# board.net
KiCad netlist of a schematic drawn in EAGLE
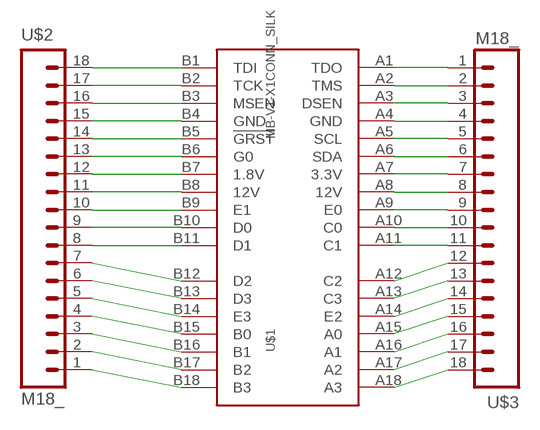
[diagram p0: schematic, sheet 1]

(export (version "E")
  (design (tool "Eeschema 10.0.6"))
  (components
    (comp (ref "U$1")
      (value "MB-V1-X1CONN_SILK")
      (footprint "eagle-import:MB-V1-X1-CONN")
      (libsource (lib "eagle-import") (part "MB-V1-X1CONN_SILK"))
    )
    (comp (ref "U$2")
      (value "M18_")
      (footprint "eagle-import:1X18")
      (libsource (lib "eagle-import") (part "M18_"))
    )
    (comp (ref "U$3")
      (value "M18_")
      (footprint "eagle-import:1X18")
      (libsource (lib "eagle-import") (part "M18_"))
    )
  )
  (nets
    (net (code "1") (name "/12V") (class "Default")
      (node (ref "U$1") (pin "A8") (pinfunction "12V_A8") (pintype "bidirectional"))
      (node (ref "U$1") (pin "B8") (pinfunction "12V_B8") (pintype "bidirectional"))
      (node (ref "U$2") (pin "11") (pinfunction "11_11") (pintype "passive"))
      (node (ref "U$3") (pin "8") (pinfunction "8_8") (pintype "passive"))
    )
    (net (code "2") (name "/GND") (class "Default")
      (node (ref "U$1") (pin "A4") (pinfunction "GND_A4") (pintype "bidirectional"))
      (node (ref "U$1") (pin "B4") (pinfunction "GND_B4") (pintype "bidirectional"))
      (node (ref "U$2") (pin "15") (pinfunction "15_15") (pintype "passive"))
      (node (ref "U$3") (pin "4") (pinfunction "4_4") (pintype "passive"))
    )
    (net (code "3") (name "Net-(U$1-1.8V)") (class "Default")
      (node (ref "U$1") (pin "B7") (pinfunction "1.8V_B7") (pintype "bidirectional"))
      (node (ref "U$2") (pin "12") (pinfunction "12_12") (pintype "passive"))
    )
    (net (code "4") (name "Net-(U$1-3.3V)") (class "Default")
      (node (ref "U$1") (pin "A7") (pinfunction "3.3V_A7") (pintype "bidirectional"))
      (node (ref "U$3") (pin "7") (pinfunction "7_7") (pintype "passive"))
    )
    (net (code "5") (name "Net-(U$1-A0)") (class "Default")
      (node (ref "U$1") (pin "A15") (pinfunction "A0_A15") (pintype "bidirectional"))
      (node (ref "U$3") (pin "15") (pinfunction "15_15") (pintype "passive"))
    )
    (net (code "6") (name "Net-(U$1-A1)") (class "Default")
      (node (ref "U$1") (pin "A16") (pinfunction "A1_A16") (pintype "bidirectional"))
      (node (ref "U$3") (pin "16") (pinfunction "16_16") (pintype "passive"))
    )
    (net (code "7") (name "Net-(U$1-A2)") (class "Default")
      (node (ref "U$1") (pin "A17") (pinfunction "A2_A17") (pintype "bidirectional"))
      (node (ref "U$3") (pin "17") (pinfunction "17_17") (pintype "passive"))
    )
    (net (code "8") (name "Net-(U$1-A3)") (class "Default")
      (node (ref "U$1") (pin "A18") (pinfunction "A3_A18") (pintype "bidirectional"))
      (node (ref "U$3") (pin "18") (pinfunction "18_18") (pintype "passive"))
    )
    (net (code "9") (name "Net-(U$1-B0)") (class "Default")
      (node (ref "U$1") (pin "B15") (pinfunction "B0_B15") (pintype "bidirectional"))
      (node (ref "U$2") (pin "4") (pinfunction "4_4") (pintype "passive"))
    )
    (net (code "10") (name "Net-(U$1-B1)") (class "Default")
      (node (ref "U$1") (pin "B16") (pinfunction "B1_B16") (pintype "bidirectional"))
      (node (ref "U$2") (pin "3") (pinfunction "3_3") (pintype "passive"))
    )
    (net (code "11") (name "Net-(U$1-B2)") (class "Default")
      (node (ref "U$1") (pin "B17") (pinfunction "B2_B17") (pintype "bidirectional"))
      (node (ref "U$2") (pin "2") (pinfunction "2_2") (pintype "passive"))
    )
    (net (code "12") (name "Net-(U$1-B3)") (class "Default")
      (node (ref "U$1") (pin "B18") (pinfunction "B3_B18") (pintype "bidirectional"))
      (node (ref "U$2") (pin "1") (pinfunction "1_1") (pintype "passive"))
    )
    (net (code "13") (name "Net-(U$1-C0)") (class "Default")
      (node (ref "U$1") (pin "A10") (pinfunction "C0_A10") (pintype "bidirectional"))
      (node (ref "U$3") (pin "10") (pinfunction "10_10") (pintype "passive"))
    )
    (net (code "14") (name "Net-(U$1-C1)") (class "Default")
      (node (ref "U$1") (pin "A11") (pinfunction "C1_A11") (pintype "bidirectional"))
      (node (ref "U$3") (pin "11") (pinfunction "11_11") (pintype "passive"))
    )
    (net (code "15") (name "Net-(U$1-C2)") (class "Default")
      (node (ref "U$1") (pin "A12") (pinfunction "C2_A12") (pintype "bidirectional"))
      (node (ref "U$3") (pin "12") (pinfunction "12_12") (pintype "passive"))
    )
    (net (code "16") (name "Net-(U$1-C3)") (class "Default")
      (node (ref "U$1") (pin "A13") (pinfunction "C3_A13") (pintype "bidirectional"))
      (node (ref "U$3") (pin "13") (pinfunction "13_13") (pintype "passive"))
    )
    (net (code "17") (name "Net-(U$1-D0)") (class "Default")
      (node (ref "U$1") (pin "B10") (pinfunction "D0_B10") (pintype "bidirectional"))
      (node (ref "U$2") (pin "9") (pinfunction "9_9") (pintype "passive"))
    )
    (net (code "18") (name "Net-(U$1-D1)") (class "Default")
      (node (ref "U$1") (pin "B11") (pinfunction "D1_B11") (pintype "bidirectional"))
      (node (ref "U$2") (pin "8") (pinfunction "8_8") (pintype "passive"))
    )
    (net (code "19") (name "Net-(U$1-D2)") (class "Default")
      (node (ref "U$1") (pin "B12") (pinfunction "D2_B12") (pintype "bidirectional"))
      (node (ref "U$2") (pin "7") (pinfunction "7_7") (pintype "passive"))
    )
    (net (code "20") (name "Net-(U$1-D3)") (class "Default")
      (node (ref "U$1") (pin "B13") (pinfunction "D3_B13") (pintype "bidirectional"))
      (node (ref "U$2") (pin "6") (pinfunction "6_6") (pintype "passive"))
    )
    (net (code "21") (name "Net-(U$1-DSEN)") (class "Default")
      (node (ref "U$1") (pin "A3") (pinfunction "DSEN_A3") (pintype "bidirectional"))
      (node (ref "U$3") (pin "3") (pinfunction "3_3") (pintype "passive"))
    )
    (net (code "22") (name "Net-(U$1-E0)") (class "Default")
      (node (ref "U$1") (pin "A9") (pinfunction "E0_A9") (pintype "bidirectional"))
      (node (ref "U$3") (pin "9") (pinfunction "9_9") (pintype "passive"))
    )
    (net (code "23") (name "Net-(U$1-E1)") (class "Default")
      (node (ref "U$1") (pin "B9") (pinfunction "E1_B9") (pintype "bidirectional"))
      (node (ref "U$2") (pin "10") (pinfunction "10_10") (pintype "passive"))
    )
    (net (code "24") (name "Net-(U$1-E2)") (class "Default")
      (node (ref "U$1") (pin "A14") (pinfunction "E2_A14") (pintype "bidirectional"))
      (node (ref "U$3") (pin "14") (pinfunction "14_14") (pintype "passive"))
    )
    (net (code "25") (name "Net-(U$1-E3)") (class "Default")
      (node (ref "U$1") (pin "B14") (pinfunction "E3_B14") (pintype "bidirectional"))
      (node (ref "U$2") (pin "5") (pinfunction "5_5") (pintype "passive"))
    )
    (net (code "26") (name "Net-(U$1-G0)") (class "Default")
      (node (ref "U$1") (pin "B6") (pinfunction "G0_B6") (pintype "bidirectional"))
      (node (ref "U$2") (pin "13") (pinfunction "13_13") (pintype "passive"))
    )
    (net (code "27") (name "Net-(U$1-MSEN)") (class "Default")
      (node (ref "U$1") (pin "B3") (pinfunction "MSEN_B3") (pintype "bidirectional"))
      (node (ref "U$2") (pin "16") (pinfunction "16_16") (pintype "passive"))
    )
    (net (code "28") (name "Net-(U$1-SCL)") (class "Default")
      (node (ref "U$1") (pin "A5") (pinfunction "SCL_A5") (pintype "bidirectional"))
      (node (ref "U$3") (pin "5") (pinfunction "5_5") (pintype "passive"))
    )
    (net (code "29") (name "Net-(U$1-SDA)") (class "Default")
      (node (ref "U$1") (pin "A6") (pinfunction "SDA_A6") (pintype "bidirectional"))
      (node (ref "U$3") (pin "6") (pinfunction "6_6") (pintype "passive"))
    )
    (net (code "30") (name "Net-(U$1-TCK)") (class "Default")
      (node (ref "U$1") (pin "B2") (pinfunction "TCK_B2") (pintype "bidirectional"))
      (node (ref "U$2") (pin "17") (pinfunction "17_17") (pintype "passive"))
    )
    (net (code "31") (name "Net-(U$1-TDI)") (class "Default")
      (node (ref "U$1") (pin "B1") (pinfunction "TDI_B1") (pintype "bidirectional"))
      (node (ref "U$2") (pin "18") (pinfunction "18_18") (pintype "passive"))
    )
    (net (code "32") (name "Net-(U$1-TDO)") (class "Default")
      (node (ref "U$1") (pin "A1") (pinfunction "TDO_A1") (pintype "bidirectional"))
      (node (ref "U$3") (pin "1") (pinfunction "1_1") (pintype "passive"))
    )
    (net (code "33") (name "Net-(U$1-TMS)") (class "Default")
      (node (ref "U$1") (pin "A2") (pinfunction "TMS_A2") (pintype "bidirectional"))
      (node (ref "U$3") (pin "2") (pinfunction "2_2") (pintype "passive"))
    )
    (net (code "34") (name "Net-(U$1-~{GRST})") (class "Default")
      (node (ref "U$1") (pin "B5") (pinfunction "~{GRST}_B5") (pintype "bidirectional"))
      (node (ref "U$2") (pin "14") (pinfunction "14_14") (pintype "passive"))
    )
  )
)
